# powerblade_test.net
KiCad netlist of a schematic drawn in EAGLE
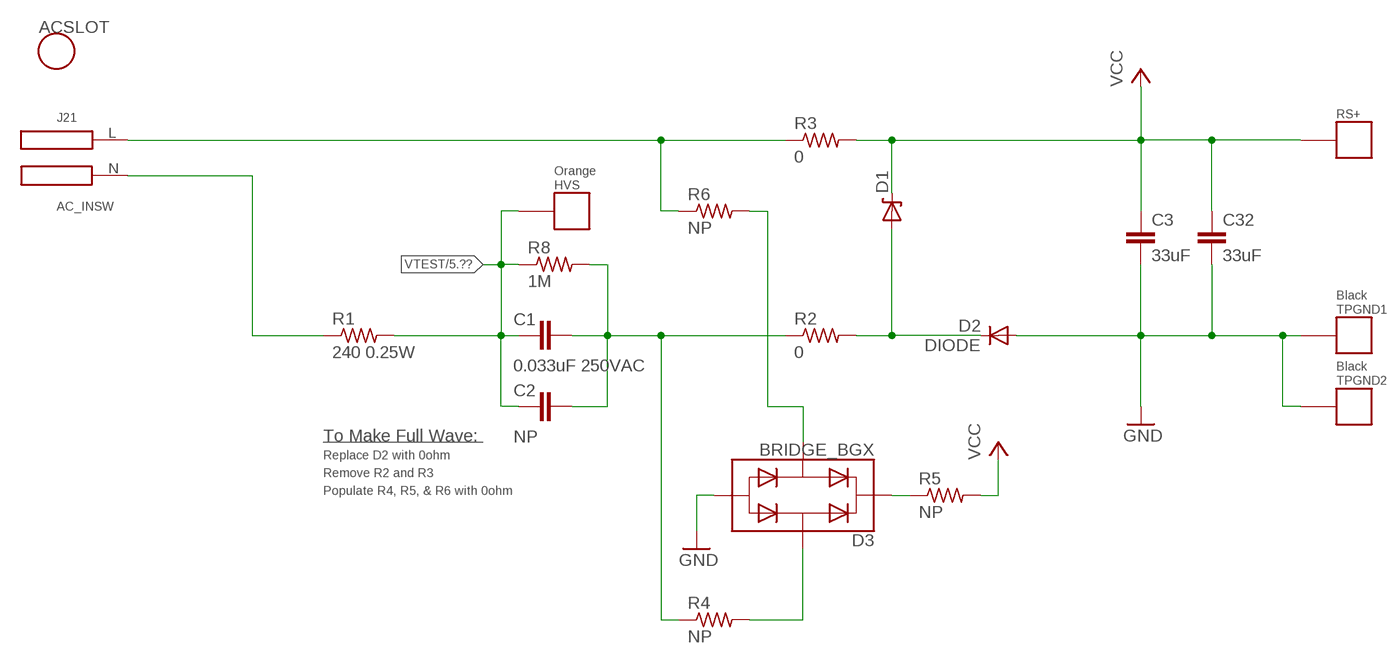
[diagram p0: schematic, sheet 1]
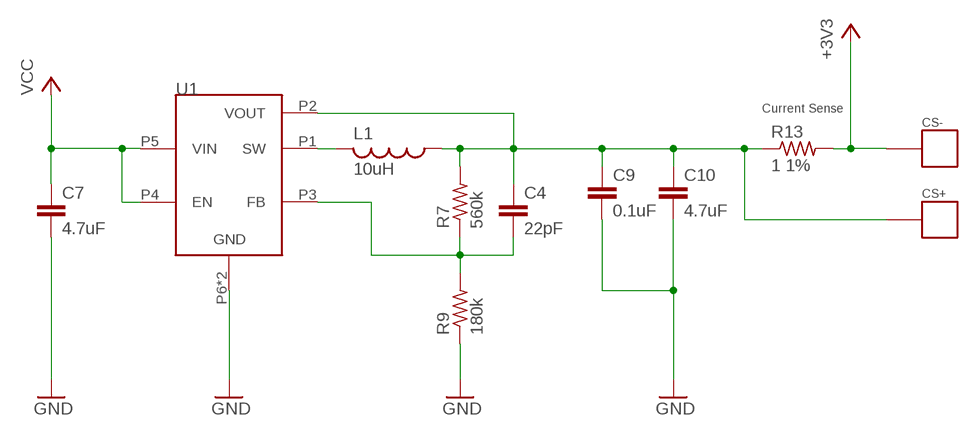
[diagram p1: schematic, sheet 2]
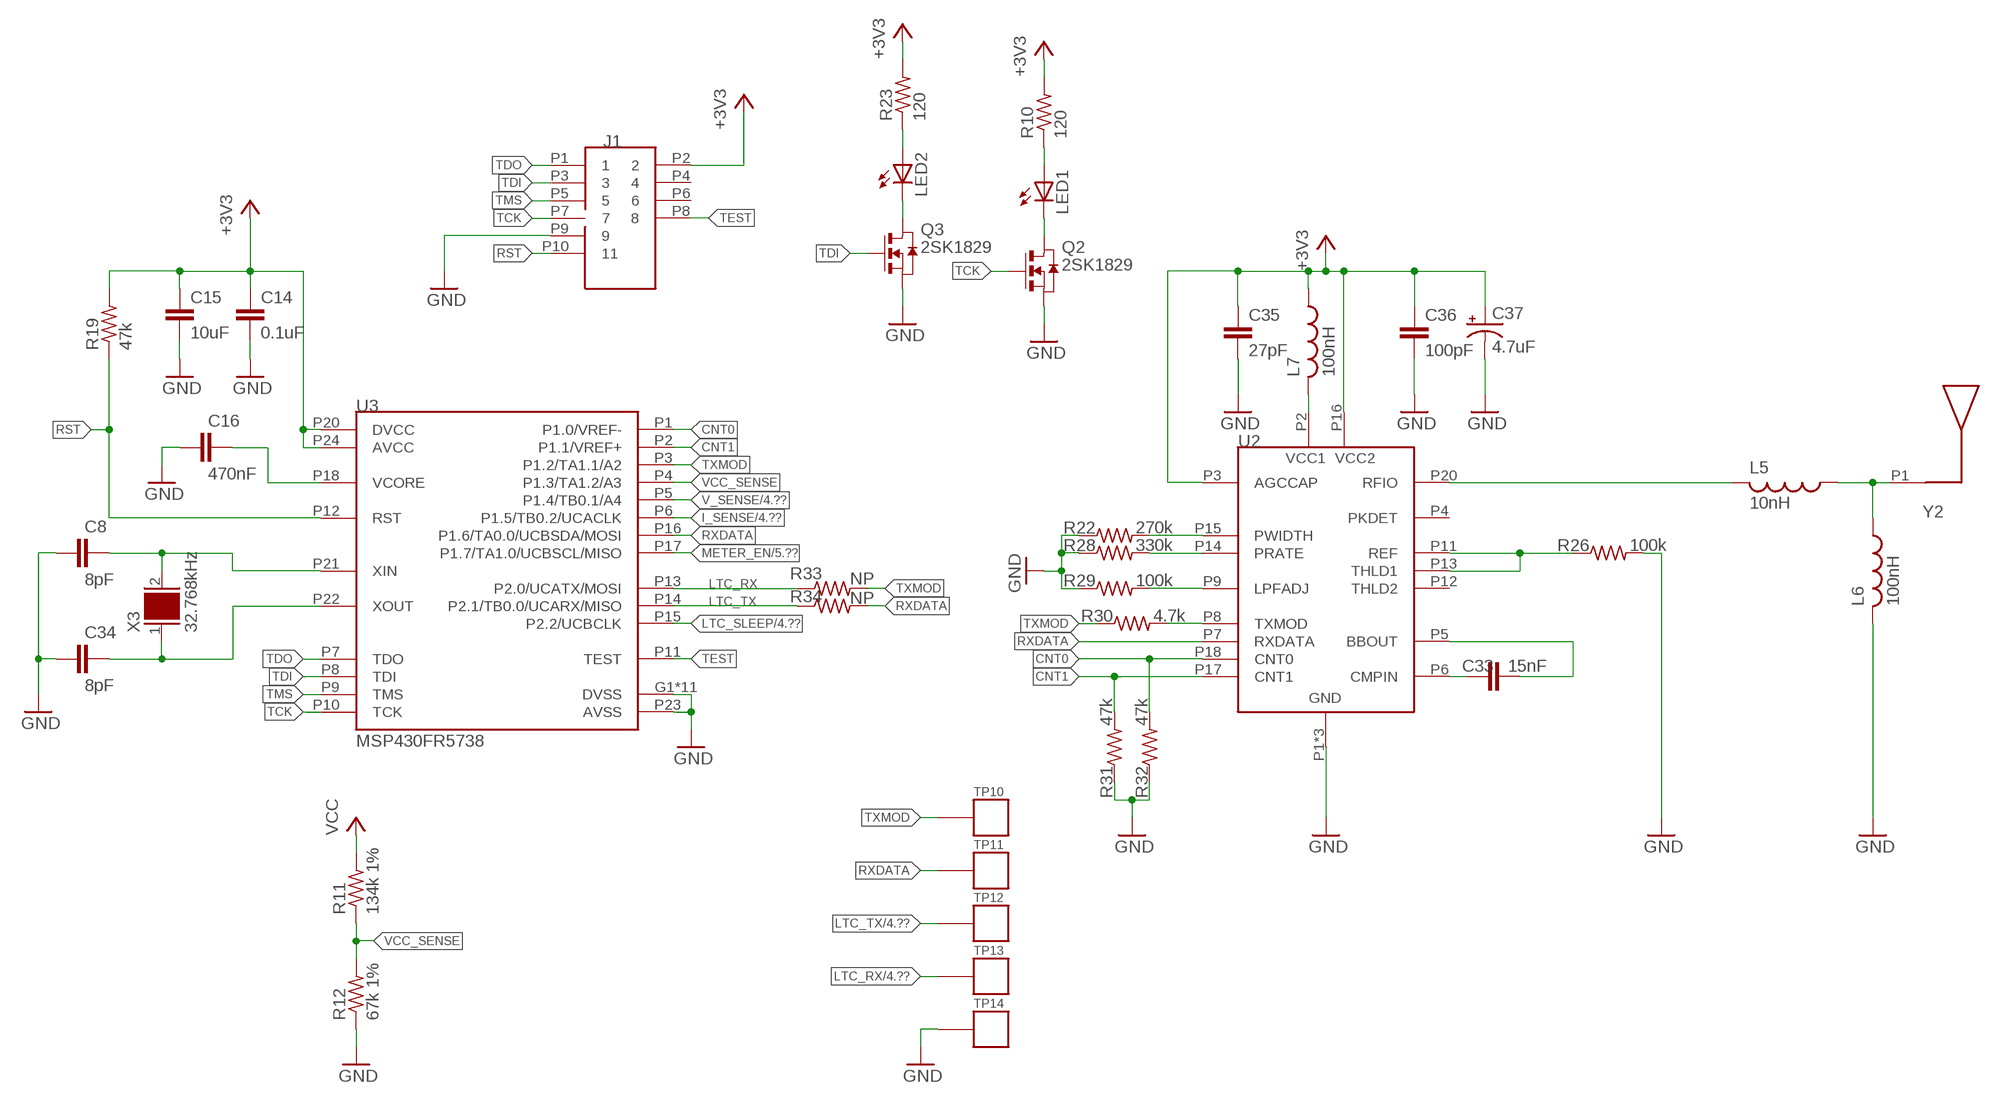
[diagram p2: schematic, sheet 3]
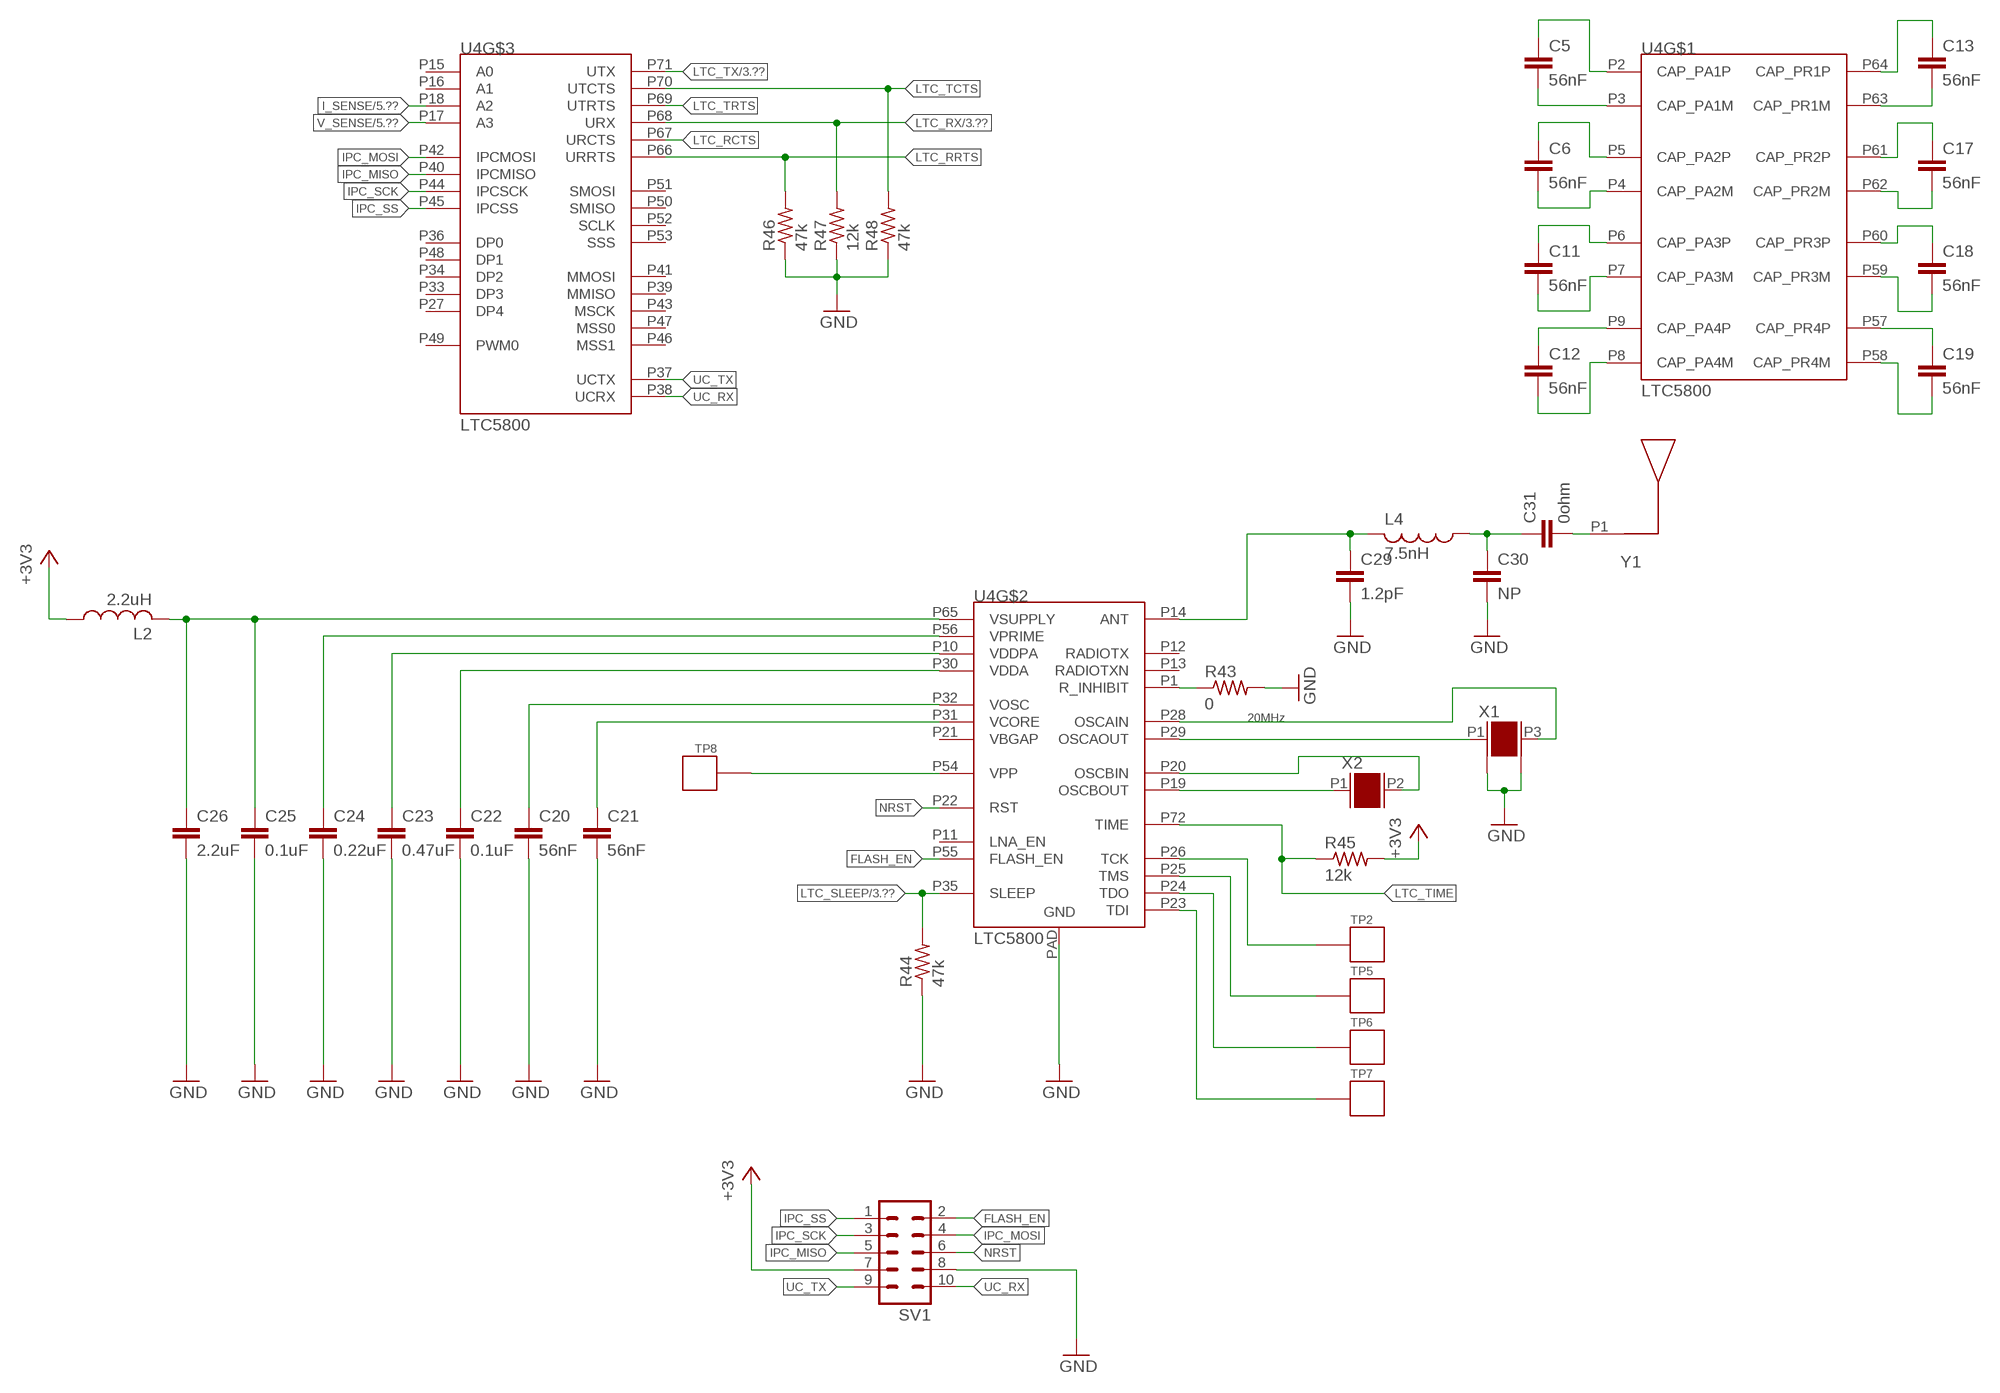
[diagram p3: schematic, sheet 4]
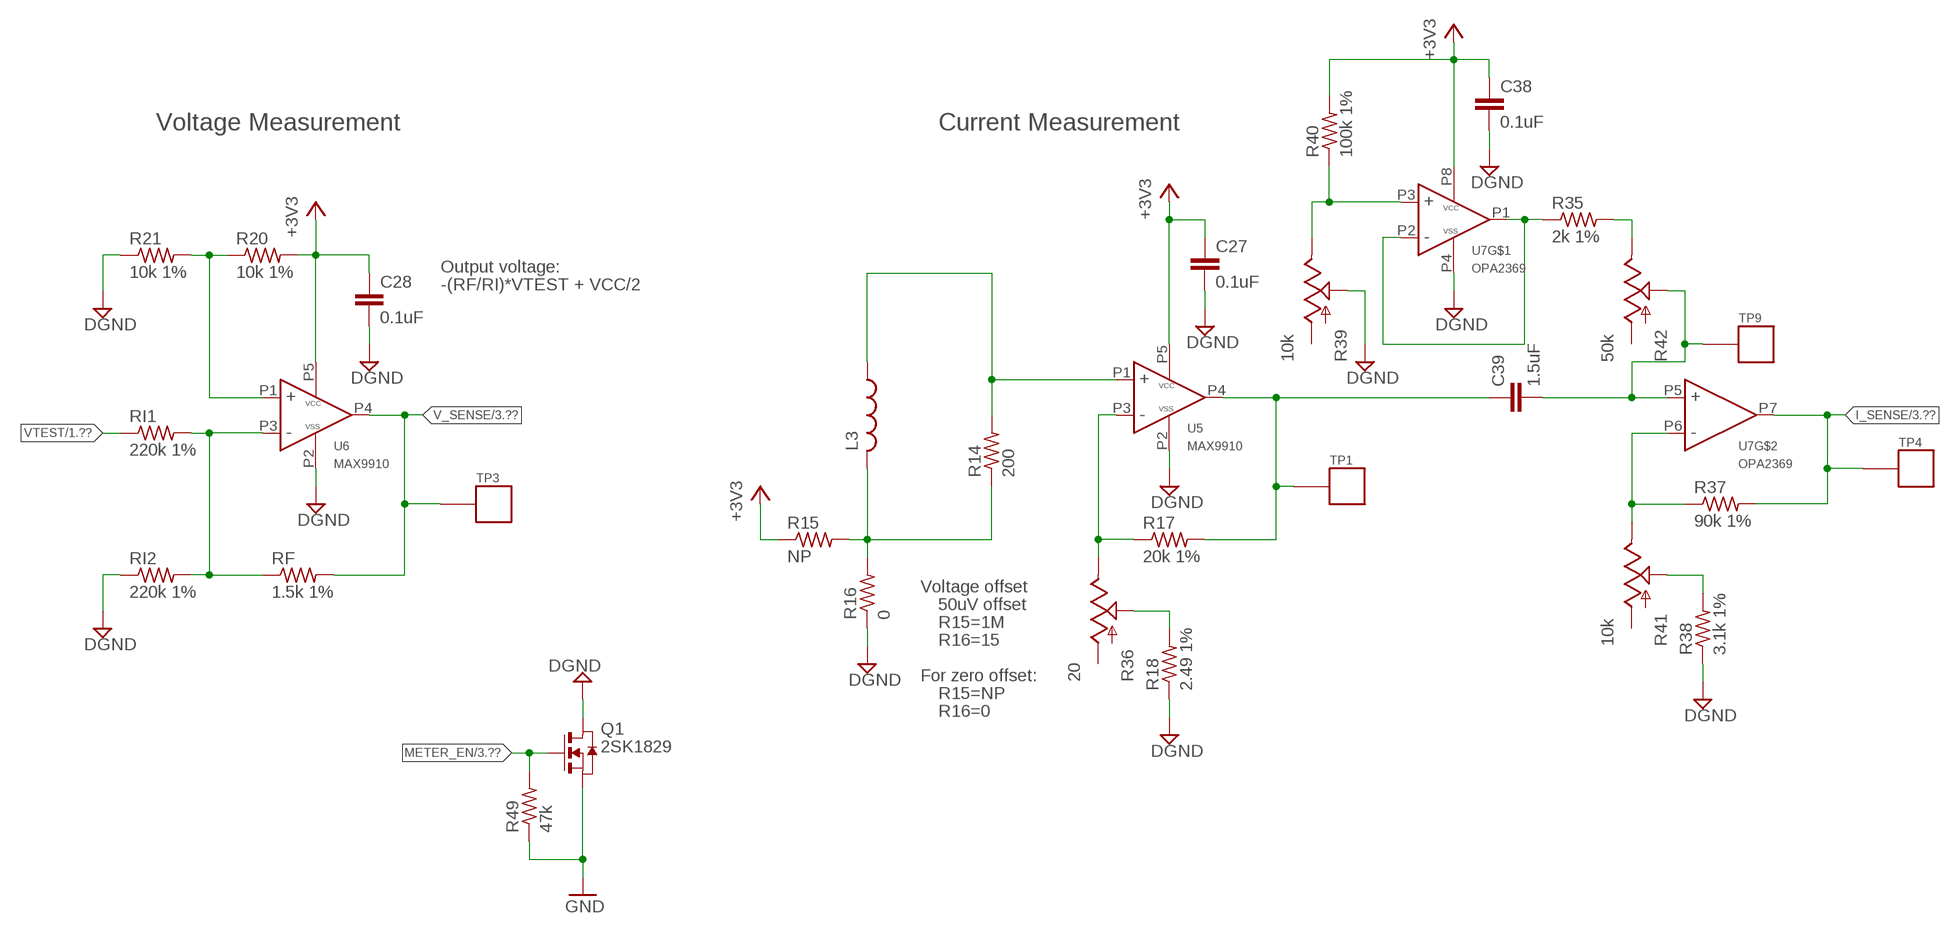
[diagram p4: schematic, sheet 5]

(export (version "E")
  (design (tool "Eeschema 10.0.6"))
  (components
    (comp (ref "C27")
      (value "0.1uF")
      (footprint "eagle-import:C0402")
      (libsource (lib "eagle-import") (part "C-EUC0402"))
    )
    (comp (ref "C28")
      (value "0.1uF")
      (footprint "eagle-import:C0402")
      (libsource (lib "eagle-import") (part "C-EUC0402"))
    )
    (comp (ref "C38")
      (value "0.1uF")
      (footprint "eagle-import:C0402")
      (libsource (lib "eagle-import") (part "C-EUC0402"))
    )
    (comp (ref "C39")
      (value "1.5uF")
      (footprint "eagle-import:C0402")
      (libsource (lib "eagle-import") (part "C-EUC0402"))
    )
    (comp (ref "L3")
      (value "L-USL0805")
      (footprint "eagle-import:L0805")
      (libsource (lib "eagle-import") (part "L-USL0805"))
    )
    (comp (ref "Q1")
      (value "2SK1829")
      (footprint "eagle-import:SC-70-3")
      (libsource (lib "eagle-import") (part "2SK1829"))
    )
    (comp (ref "R14")
      (value "200")
      (footprint "eagle-import:R0402")
      (libsource (lib "eagle-import") (part "R-US_R0402"))
    )
    (comp (ref "R15")
      (value "NP")
      (footprint "eagle-import:R0402")
      (libsource (lib "eagle-import") (part "R-US_R0402"))
    )
    (comp (ref "R16")
      (value "0")
      (footprint "eagle-import:R0402")
      (libsource (lib "eagle-import") (part "R-US_R0402"))
    )
    (comp (ref "R17")
      (value "20k 1%")
      (footprint "eagle-import:R0402")
      (libsource (lib "eagle-import") (part "R-US_R0402"))
    )
    (comp (ref "R18")
      (value "2.49 1%")
      (footprint "eagle-import:R0402")
      (libsource (lib "eagle-import") (part "R-US_R0402"))
    )
    (comp (ref "R20")
      (value "10k 1%")
      (footprint "eagle-import:R0402")
      (libsource (lib "eagle-import") (part "R-US_R0402"))
    )
    (comp (ref "R21")
      (value "10k 1%")
      (footprint "eagle-import:R0402")
      (libsource (lib "eagle-import") (part "R-US_R0402"))
    )
    (comp (ref "R35")
      (value "2k 1%")
      (footprint "eagle-import:R0402")
      (libsource (lib "eagle-import") (part "R-US_R0402"))
    )
    (comp (ref "R36")
      (value "20")
      (footprint "eagle-import:3313_POT")
      (libsource (lib "eagle-import") (part "3313_POT"))
    )
    (comp (ref "R37")
      (value "90k 1%")
      (footprint "eagle-import:R0402")
      (libsource (lib "eagle-import") (part "R-US_R0402"))
    )
    (comp (ref "R38")
      (value "3.1k 1%")
      (footprint "eagle-import:R0603")
      (libsource (lib "eagle-import") (part "R-US_R0603"))
    )
    (comp (ref "R39")
      (value "10k")
      (footprint "eagle-import:3313_POT")
      (libsource (lib "eagle-import") (part "3313_POT"))
    )
    (comp (ref "R40")
      (value "100k 1%")
      (footprint "eagle-import:R0402")
      (libsource (lib "eagle-import") (part "R-US_R0402"))
    )
    (comp (ref "R41")
      (value "10k")
      (footprint "eagle-import:3313_POT")
      (libsource (lib "eagle-import") (part "3313_POT"))
    )
    (comp (ref "R42")
      (value "50k")
      (footprint "eagle-import:3313_POT")
      (libsource (lib "eagle-import") (part "3313_POT"))
    )
    (comp (ref "R49")
      (value "47k")
      (footprint "eagle-import:R0603")
      (libsource (lib "eagle-import") (part "R-US_R0603"))
    )
    (comp (ref "RF")
      (value "1.5k 1%")
      (footprint "eagle-import:R0402")
      (libsource (lib "eagle-import") (part "R-US_R0402"))
    )
    (comp (ref "RI1")
      (value "220k 1%")
      (footprint "eagle-import:R0402")
      (libsource (lib "eagle-import") (part "R-US_R0402"))
    )
    (comp (ref "RI2")
      (value "220k 1%")
      (footprint "eagle-import:R0402")
      (libsource (lib "eagle-import") (part "R-US_R0402"))
    )
    (comp (ref "TP1")
      (value "TP_MULT")
      (footprint "eagle-import:TP_MULT")
      (libsource (lib "eagle-import") (part "TP_MULT"))
    )
    (comp (ref "TP3")
      (value "TP_MULT")
      (footprint "eagle-import:TP_MULT")
      (libsource (lib "eagle-import") (part "TP_MULT"))
    )
    (comp (ref "TP4")
      (value "TP_MULT")
      (footprint "eagle-import:TP_MULT")
      (libsource (lib "eagle-import") (part "TP_MULT"))
    )
    (comp (ref "TP9")
      (value "TP_MULT")
      (footprint "eagle-import:TP_MULT")
      (libsource (lib "eagle-import") (part "TP_MULT"))
    )
    (comp (ref "U5")
      (value "MAX9910")
      (footprint "eagle-import:SC70-5")
      (libsource (lib "eagle-import") (part "MAX9910"))
    )
    (comp (ref "U6")
      (value "MAX9910")
      (footprint "eagle-import:SC70-5")
      (libsource (lib "eagle-import") (part "MAX9910"))
    )
    (comp (ref "U7")
      (value "OPA2369")
      (footprint "eagle-import:SOT-23-8")
      (libsource (lib "eagle-import") (part "OPA2369"))
    )
    (comp (ref "C5")
      (value "56nF")
      (footprint "eagle-import:C0402")
      (libsource (lib "eagle-import") (part "C-EUC0402"))
    )
    (comp (ref "C6")
      (value "56nF")
      (footprint "eagle-import:C0402")
      (libsource (lib "eagle-import") (part "C-EUC0402"))
    )
    (comp (ref "C11")
      (value "56nF")
      (footprint "eagle-import:C0402")
      (libsource (lib "eagle-import") (part "C-EUC0402"))
    )
    (comp (ref "C12")
      (value "56nF")
      (footprint "eagle-import:C0402")
      (libsource (lib "eagle-import") (part "C-EUC0402"))
    )
    (comp (ref "C13")
      (value "56nF")
      (footprint "eagle-import:C0402")
      (libsource (lib "eagle-import") (part "C-EUC0402"))
    )
    (comp (ref "C17")
      (value "56nF")
      (footprint "eagle-import:C0402")
      (libsource (lib "eagle-import") (part "C-EUC0402"))
    )
    (comp (ref "C18")
      (value "56nF")
      (footprint "eagle-import:C0402")
      (libsource (lib "eagle-import") (part "C-EUC0402"))
    )
    (comp (ref "C19")
      (value "56nF")
      (footprint "eagle-import:C0402")
      (libsource (lib "eagle-import") (part "C-EUC0402"))
    )
    (comp (ref "C20")
      (value "56nF")
      (footprint "eagle-import:C0402")
      (libsource (lib "eagle-import") (part "C-EUC0402"))
    )
    (comp (ref "C21")
      (value "56nF")
      (footprint "eagle-import:C0402")
      (libsource (lib "eagle-import") (part "C-EUC0402"))
    )
    (comp (ref "C22")
      (value "0.1uF")
      (footprint "eagle-import:C0603")
      (libsource (lib "eagle-import") (part "C-EUC0603"))
    )
    (comp (ref "C23")
      (value "0.47uF")
      (footprint "eagle-import:C0603")
      (libsource (lib "eagle-import") (part "C-EUC0603"))
    )
    (comp (ref "C24")
      (value "0.22uF")
      (footprint "eagle-import:C0603")
      (libsource (lib "eagle-import") (part "C-EUC0603"))
    )
    (comp (ref "C25")
      (value "0.1uF")
      (footprint "eagle-import:C0603")
      (libsource (lib "eagle-import") (part "C-EUC0603"))
    )
    (comp (ref "C26")
      (value "2.2uF")
      (footprint "eagle-import:C0603")
      (libsource (lib "eagle-import") (part "C-EUC0603"))
    )
    (comp (ref "C29")
      (value "1.2pF")
      (footprint "eagle-import:C0402")
      (libsource (lib "eagle-import") (part "C-EUC0402"))
    )
    (comp (ref "C30")
      (value "NP")
      (footprint "eagle-import:C0402")
      (libsource (lib "eagle-import") (part "C-EUC0402"))
    )
    (comp (ref "C31")
      (value "0ohm")
      (footprint "eagle-import:C0402")
      (libsource (lib "eagle-import") (part "C-EUC0402"))
    )
    (comp (ref "L2")
      (value "2.2uH")
      (footprint "eagle-import:L0603")
      (libsource (lib "eagle-import") (part "L-USL0603"))
    )
    (comp (ref "L4")
      (value "7.5nH")
      (footprint "eagle-import:L0402")
      (libsource (lib "eagle-import") (part "L-USL0402"))
    )
    (comp (ref "R43")
      (value "0")
      (footprint "eagle-import:R0402")
      (libsource (lib "eagle-import") (part "R-US_R0402"))
    )
    (comp (ref "R44")
      (value "47k")
      (footprint "eagle-import:R0402")
      (libsource (lib "eagle-import") (part "R-US_R0402"))
    )
    (comp (ref "R45")
      (value "12k")
      (footprint "eagle-import:R0402")
      (libsource (lib "eagle-import") (part "R-US_R0402"))
    )
    (comp (ref "R46")
      (value "47k")
      (footprint "eagle-import:R0402")
      (libsource (lib "eagle-import") (part "R-US_R0402"))
    )
    (comp (ref "R47")
      (value "12k")
      (footprint "eagle-import:R0402")
      (libsource (lib "eagle-import") (part "R-US_R0402"))
    )
    (comp (ref "R48")
      (value "47k")
      (footprint "eagle-import:R0402")
      (libsource (lib "eagle-import") (part "R-US_R0402"))
    )
    (comp (ref "SV1")
      (value "MA05-2KEY")
      (footprint "eagle-import:MA05-2_KEY")
      (libsource (lib "eagle-import") (part "MA05-2KEY"))
    )
    (comp (ref "TP2")
      (value "TP_SMD")
      (footprint "eagle-import:TP_SMD")
      (libsource (lib "eagle-import") (part "TP_SMD"))
    )
    (comp (ref "TP5")
      (value "TP_SMD")
      (footprint "eagle-import:TP_SMD")
      (libsource (lib "eagle-import") (part "TP_SMD"))
    )
    (comp (ref "TP6")
      (value "TP_SMD")
      (footprint "eagle-import:TP_SMD")
      (libsource (lib "eagle-import") (part "TP_SMD"))
    )
    (comp (ref "TP7")
      (value "TP_SMD")
      (footprint "eagle-import:TP_SMD")
      (libsource (lib "eagle-import") (part "TP_SMD"))
    )
    (comp (ref "TP8")
      (value "TP_STD")
      (footprint "eagle-import:TP")
      (libsource (lib "eagle-import") (part "TP_STD"))
    )
    (comp (ref "U4")
      (value "LTC5800")
      (footprint "eagle-import:QFN-72")
      (libsource (lib "eagle-import") (part "LTC5800"))
    )
    (comp (ref "X1")
      (value "ABM8G")
      (footprint "eagle-import:ABM8G")
      (libsource (lib "eagle-import") (part "ABM8G"))
    )
    (comp (ref "X2")
      (value "ABS07")
      (footprint "eagle-import:ABS07")
      (libsource (lib "eagle-import") (part "ABS07"))
    )
    (comp (ref "Y1")
      (value "UREACH_XTEND")
      (footprint "eagle-import:UREACH_XTEND")
      (libsource (lib "eagle-import") (part "UREACH_XTEND"))
    )
    (comp (ref "ACSLOT")
      (value "AC_NODIM")
      (footprint "eagle-import:AC3_NODIM")
      (libsource (lib "eagle-import") (part "AC_NODIM"))
    )
    (comp (ref "C1")
      (value "0.033uF 250VAC")
      (footprint "eagle-import:C2220K")
      (libsource (lib "eagle-import") (part "C-EUC2220K"))
    )
    (comp (ref "C2")
      (value "NP")
      (footprint "eagle-import:C2220K")
      (libsource (lib "eagle-import") (part "C-EUC2220K"))
    )
    (comp (ref "C3")
      (value "33uF")
      (footprint "eagle-import:C0603")
      (libsource (lib "eagle-import") (part "C-EUC0603"))
    )
    (comp (ref "C32")
      (value "33uF")
      (footprint "eagle-import:C0603")
      (libsource (lib "eagle-import") (part "C-EUC0603"))
    )
    (comp (ref "D1")
      (value "ZENERBZT52")
      (footprint "eagle-import:BZT52")
      (fields (field (name "DIGIKEY") "NP"))
      (libsource (lib "eagle-import") (part "ZENERBZT52"))
    )
    (comp (ref "D2")
      (value "DIODE")
      (footprint "eagle-import:BAS521")
      (fields (field (name "DIGIKEY") "NP"))
      (libsource (lib "eagle-import") (part "DIODE"))
    )
    (comp (ref "D3")
      (value "BRIDGE_BGX")
      (footprint "eagle-import:TO-253-4")
      (fields (field (name "DIGIKEY") "NP"))
      (libsource (lib "eagle-import") (part "BRIDGE_BGX"))
    )
    (comp (ref "HVS")
      (value "TP_MULT")
      (footprint "eagle-import:TP_MULT")
      (libsource (lib "eagle-import") (part "TP_MULT"))
    )
    (comp (ref "J21")
      (value "AC_INSW")
      (footprint "eagle-import:AC_DC21")
      (fields (field (name "DIGIKEY") "NP"))
      (libsource (lib "eagle-import") (part "AC_INSW"))
    )
    (comp (ref "R1")
      (value "240 0.25W")
      (footprint "eagle-import:R0603")
      (libsource (lib "eagle-import") (part "R-US_R0603"))
    )
    (comp (ref "R2")
      (value "0")
      (footprint "eagle-import:R0603")
      (libsource (lib "eagle-import") (part "R-US_R0603"))
    )
    (comp (ref "R3")
      (value "0")
      (footprint "eagle-import:R0603")
      (libsource (lib "eagle-import") (part "R-US_R0603"))
    )
    (comp (ref "R4")
      (value "NP")
      (footprint "eagle-import:R0603")
      (libsource (lib "eagle-import") (part "R-US_R0603"))
    )
    (comp (ref "R5")
      (value "NP")
      (footprint "eagle-import:R0603")
      (libsource (lib "eagle-import") (part "R-US_R0603"))
    )
    (comp (ref "R6")
      (value "NP")
      (footprint "eagle-import:R0603")
      (libsource (lib "eagle-import") (part "R-US_R0603"))
    )
    (comp (ref "R8")
      (value "1M")
      (footprint "eagle-import:R0603")
      (libsource (lib "eagle-import") (part "R-US_R0603"))
    )
    (comp (ref "RS+")
      (value "TP_MULT")
      (footprint "eagle-import:TP_MULT")
      (libsource (lib "eagle-import") (part "TP_MULT"))
    )
    (comp (ref "TPGND1")
      (value "TP_MULT")
      (footprint "eagle-import:TP_MULT")
      (libsource (lib "eagle-import") (part "TP_MULT"))
    )
    (comp (ref "TPGND2")
      (value "TP_MULT")
      (footprint "eagle-import:TP_MULT")
      (libsource (lib "eagle-import") (part "TP_MULT"))
    )
    (comp (ref "C4")
      (value "22pF")
      (footprint "eagle-import:C0402")
      (libsource (lib "eagle-import") (part "C-EUC0402"))
    )
    (comp (ref "C7")
      (value "4.7uF")
      (footprint "eagle-import:C0603")
      (libsource (lib "eagle-import") (part "C-EUC0603"))
    )
    (comp (ref "C9")
      (value "0.1uF")
      (footprint "eagle-import:C0402")
      (libsource (lib "eagle-import") (part "C-EUC0402"))
    )
    (comp (ref "C10")
      (value "4.7uF")
      (footprint "eagle-import:C0402")
      (libsource (lib "eagle-import") (part "C-EUC0402"))
    )
    (comp (ref "CS+")
      (value "TP_MULT")
      (footprint "eagle-import:TP_MULT")
      (libsource (lib "eagle-import") (part "TP_MULT"))
    )
    (comp (ref "CS-")
      (value "TP_MULT")
      (footprint "eagle-import:TP_MULT")
      (libsource (lib "eagle-import") (part "TP_MULT"))
    )
    (comp (ref "L1")
      (value "10uH")
      (footprint "eagle-import:L0805")
      (libsource (lib "eagle-import") (part "L-USL0805"))
    )
    (comp (ref "R7")
      (value "560k")
      (footprint "eagle-import:R0402")
      (libsource (lib "eagle-import") (part "R-US_R0402"))
    )
    (comp (ref "R9")
      (value "180k")
      (footprint "eagle-import:R0402")
      (libsource (lib "eagle-import") (part "R-US_R0402"))
    )
    (comp (ref "R13")
      (value "1 1%")
      (footprint "eagle-import:R0603")
      (libsource (lib "eagle-import") (part "R-US_R0603"))
    )
    (comp (ref "U1")
      (value "TPS62122")
      (footprint "eagle-import:WDFN-6")
      (libsource (lib "eagle-import") (part "TPS62122"))
    )
    (comp (ref "C8")
      (value "8pF")
      (footprint "eagle-import:C0603")
      (libsource (lib "eagle-import") (part "C-EUC0603"))
    )
    (comp (ref "C14")
      (value "0.1uF")
      (footprint "eagle-import:C0603")
      (libsource (lib "eagle-import") (part "C-EUC0603"))
    )
    (comp (ref "C15")
      (value "10uF")
      (footprint "eagle-import:C0603")
      (libsource (lib "eagle-import") (part "C-EUC0603"))
    )
    (comp (ref "C16")
      (value "470nF")
      (footprint "eagle-import:C0603")
      (libsource (lib "eagle-import") (part "C-EUC0603"))
    )
    (comp (ref "C33")
      (value "15nF")
      (footprint "eagle-import:C0603")
      (libsource (lib "eagle-import") (part "C-EUC0603"))
    )
    (comp (ref "C34")
      (value "8pF")
      (footprint "eagle-import:C0603")
      (libsource (lib "eagle-import") (part "C-EUC0603"))
    )
    (comp (ref "C35")
      (value "27pF")
      (footprint "eagle-import:C0603")
      (libsource (lib "eagle-import") (part "C-EUC0603"))
    )
    (comp (ref "C36")
      (value "100pF")
      (footprint "eagle-import:C0603")
      (libsource (lib "eagle-import") (part "C-EUC0603"))
    )
    (comp (ref "C37")
      (value "4.7uF")
      (footprint "eagle-import:CPOL-0805")
      (libsource (lib "eagle-import") (part "CPOL-US0805"))
    )
    (comp (ref "J1")
      (value "JTAG_14PIN_IDC")
      (footprint "eagle-import:TC2050-IDC-430")
      (libsource (lib "eagle-import") (part "JTAG_14PIN_IDC"))
    )
    (comp (ref "L5")
      (value "10nH")
      (footprint "eagle-import:L0402")
      (libsource (lib "eagle-import") (part "L-USL0402"))
    )
    (comp (ref "L6")
      (value "100nH")
      (footprint "eagle-import:L0402")
      (libsource (lib "eagle-import") (part "L-USL0402"))
    )
    (comp (ref "L7")
      (value "100nH")
      (footprint "eagle-import:L0603")
      (libsource (lib "eagle-import") (part "L-USL0603"))
    )
    (comp (ref "LED1")
      (value "LED0603")
      (footprint "eagle-import:LED-0603")
      (libsource (lib "eagle-import") (part "LED0603"))
    )
    (comp (ref "LED2")
      (value "LED0603")
      (footprint "eagle-import:LED-0603")
      (libsource (lib "eagle-import") (part "LED0603"))
    )
    (comp (ref "Q2")
      (value "2SK1829")
      (footprint "eagle-import:SC-70-3")
      (libsource (lib "eagle-import") (part "2SK1829"))
    )
    (comp (ref "Q3")
      (value "2SK1829")
      (footprint "eagle-import:SC-70-3")
      (libsource (lib "eagle-import") (part "2SK1829"))
    )
    (comp (ref "R10")
      (value "120")
      (footprint "eagle-import:R0603")
      (libsource (lib "eagle-import") (part "R-US_R0603"))
    )
    (comp (ref "R11")
      (value "134k 1%")
      (footprint "eagle-import:R0603")
      (libsource (lib "eagle-import") (part "R-US_R0603"))
    )
    (comp (ref "R12")
      (value "67k 1%")
      (footprint "eagle-import:R0603")
      (libsource (lib "eagle-import") (part "R-US_R0603"))
    )
    (comp (ref "R19")
      (value "47k")
      (footprint "eagle-import:R0603")
      (libsource (lib "eagle-import") (part "R-US_R0603"))
    )
    (comp (ref "R22")
      (value "270k")
      (footprint "eagle-import:R0603")
      (libsource (lib "eagle-import") (part "R-US_R0603"))
    )
    (comp (ref "R23")
      (value "120")
      (footprint "eagle-import:R0603")
      (libsource (lib "eagle-import") (part "R-US_R0603"))
    )
    (comp (ref "R26")
      (value "100k")
      (footprint "eagle-import:R0603")
      (libsource (lib "eagle-import") (part "R-US_R0603"))
    )
    (comp (ref "R28")
      (value "330k")
      (footprint "eagle-import:R0603")
      (libsource (lib "eagle-import") (part "R-US_R0603"))
    )
    (comp (ref "R29")
      (value "100k")
      (footprint "eagle-import:R0603")
      (libsource (lib "eagle-import") (part "R-US_R0603"))
    )
    (comp (ref "R30")
      (value "4.7k")
      (footprint "eagle-import:R0603")
      (libsource (lib "eagle-import") (part "R-US_R0603"))
    )
    (comp (ref "R31")
      (value "47k")
      (footprint "eagle-import:R0603")
      (libsource (lib "eagle-import") (part "R-US_R0603"))
    )
    (comp (ref "R32")
      (value "47k")
      (footprint "eagle-import:R0603")
      (libsource (lib "eagle-import") (part "R-US_R0603"))
    )
    (comp (ref "R33")
      (value "NP")
      (footprint "eagle-import:R0603")
      (libsource (lib "eagle-import") (part "R-US_R0603"))
    )
    (comp (ref "R34")
      (value "NP")
      (footprint "eagle-import:R0603")
      (libsource (lib "eagle-import") (part "R-US_R0603"))
    )
    (comp (ref "TP10")
      (value "TP_STD")
      (footprint "eagle-import:TP")
      (libsource (lib "eagle-import") (part "TP_STD"))
    )
    (comp (ref "TP11")
      (value "TP_STD")
      (footprint "eagle-import:TP")
      (libsource (lib "eagle-import") (part "TP_STD"))
    )
    (comp (ref "TP12")
      (value "TP_STD")
      (footprint "eagle-import:TP")
      (libsource (lib "eagle-import") (part "TP_STD"))
    )
    (comp (ref "TP13")
      (value "TP_STD")
      (footprint "eagle-import:TP")
      (libsource (lib "eagle-import") (part "TP_STD"))
    )
    (comp (ref "TP14")
      (value "TP_STD")
      (footprint "eagle-import:TP")
      (libsource (lib "eagle-import") (part "TP_STD"))
    )
    (comp (ref "U2")
      (value "TR1000")
      (footprint "eagle-import:SM-20H")
      (libsource (lib "eagle-import") (part "TR1000"))
    )
    (comp (ref "U3")
      (value "MSP430FR5738")
      (footprint "eagle-import:VQFN-24")
      (libsource (lib "eagle-import") (part "MSP430FR5738"))
    )
    (comp (ref "X3")
      (value "32.768kHz")
      (footprint "eagle-import:0805")
      (libsource (lib "eagle-import") (part "CRYSTAL_0805"))
    )
    (comp (ref "Y2")
      (value "ANT-916")
      (footprint "eagle-import:ANT-916")
      (libsource (lib "eagle-import") (part "ANT-916"))
    )
  )
  (nets
    (net (code "1") (name "+3V3") (class "Default")
      (node (ref "C14") (pin "1") (pinfunction "1_1") (pintype "passive"))
      (node (ref "C15") (pin "1") (pinfunction "1_1") (pintype "passive"))
      (node (ref "C27") (pin "1") (pinfunction "1_1") (pintype "passive"))
      (node (ref "C28") (pin "1") (pinfunction "1_1") (pintype "passive"))
      (node (ref "C35") (pin "1") (pinfunction "1_1") (pintype "passive"))
      (node (ref "C36") (pin "1") (pinfunction "1_1") (pintype "passive"))
      (node (ref "C37") (pin "+") (pinfunction "+_+") (pintype "passive"))
      (node (ref "C38") (pin "1") (pinfunction "1_1") (pintype "passive"))
      (node (ref "CS-") (pin "P$1") (pinfunction "P$1_P$1") (pintype "bidirectional"))
      (node (ref "J1") (pin "P2") (pinfunction "2_P2") (pintype "bidirectional"))
      (node (ref "L2") (pin "1") (pinfunction "1_1") (pintype "passive"))
      (node (ref "L7") (pin "1") (pinfunction "1_1") (pintype "passive"))
      (node (ref "R10") (pin "2") (pinfunction "2_2") (pintype "passive"))
      (node (ref "R13") (pin "2") (pinfunction "2_2") (pintype "passive"))
      (node (ref "R15") (pin "1") (pinfunction "1_1") (pintype "passive"))
      (node (ref "R19") (pin "2") (pinfunction "2_2") (pintype "passive"))
      (node (ref "R20") (pin "2") (pinfunction "2_2") (pintype "passive"))
      (node (ref "R23") (pin "2") (pinfunction "2_2") (pintype "passive"))
      (node (ref "R40") (pin "2") (pinfunction "2_2") (pintype "passive"))
      (node (ref "R45") (pin "2") (pinfunction "2_2") (pintype "passive"))
      (node (ref "SV1") (pin "7") (pinfunction "7_7") (pintype "passive"))
      (node (ref "U2") (pin "P16") (pinfunction "VCC2_P16") (pintype "bidirectional"))
      (node (ref "U2") (pin "P3") (pinfunction "AGCCAP_P3") (pintype "bidirectional"))
      (node (ref "U3") (pin "P20") (pinfunction "DVCC_P20") (pintype "bidirectional"))
      (node (ref "U3") (pin "P24") (pinfunction "AVCC_P24") (pintype "bidirectional"))
      (node (ref "U5") (pin "P5") (pinfunction "VCC_P5") (pintype "bidirectional"))
      (node (ref "U6") (pin "P5") (pinfunction "VCC_P5") (pintype "bidirectional"))
      (node (ref "U7") (pin "P8") (pinfunction "VCC_P8") (pintype "bidirectional"))
    )
    (net (code "2") (name "CNT0") (class "Default")
      (node (ref "R32") (pin "2") (pinfunction "2_2") (pintype "passive"))
      (node (ref "U2") (pin "P18") (pinfunction "CNT0_P18") (pintype "bidirectional"))
      (node (ref "U3") (pin "P1") (pinfunction "P1.0/VREF-_P1") (pintype "bidirectional"))
    )
    (net (code "3") (name "CNT1") (class "Default")
      (node (ref "R31") (pin "2") (pinfunction "2_2") (pintype "passive"))
      (node (ref "U2") (pin "P17") (pinfunction "CNT1_P17") (pintype "bidirectional"))
      (node (ref "U3") (pin "P2") (pinfunction "P1.1/VREF+_P2") (pintype "bidirectional"))
    )
    (net (code "4") (name "DGND") (class "Default")
      (node (ref "C27") (pin "2") (pinfunction "2_2") (pintype "passive"))
      (node (ref "C28") (pin "2") (pinfunction "2_2") (pintype "passive"))
      (node (ref "C38") (pin "2") (pinfunction "2_2") (pintype "passive"))
      (node (ref "Q1") (pin "P3") (pinfunction "D_P3") (pintype "passive"))
      (node (ref "R16") (pin "1") (pinfunction "1_1") (pintype "passive"))
      (node (ref "R18") (pin "1") (pinfunction "1_1") (pintype "passive"))
      (node (ref "R21") (pin "1") (pinfunction "1_1") (pintype "passive"))
      (node (ref "R38") (pin "1") (pinfunction "1_1") (pintype "passive"))
      (node (ref "R39") (pin "PW") (pinfunction "PW_PW") (pintype "passive"))
      (node (ref "RI2") (pin "1") (pinfunction "1_1") (pintype "passive"))
      (node (ref "U5") (pin "P2") (pinfunction "VSS_P2") (pintype "bidirectional"))
      (node (ref "U6") (pin "P2") (pinfunction "VSS_P2") (pintype "bidirectional"))
      (node (ref "U7") (pin "P4") (pinfunction "VSS_P4") (pintype "bidirectional"))
    )
    (net (code "5") (name "FLASH_EN") (class "Default")
      (node (ref "SV1") (pin "2") (pinfunction "2_2") (pintype "passive"))
      (node (ref "U4") (pin "P55") (pinfunction "FLASH_EN_P55") (pintype "bidirectional"))
    )
    (net (code "6") (name "GND") (class "Default")
      (node (ref "C10") (pin "2") (pinfunction "2_2") (pintype "passive"))
      (node (ref "C14") (pin "2") (pinfunction "2_2") (pintype "passive"))
      (node (ref "C15") (pin "2") (pinfunction "2_2") (pintype "passive"))
      (node (ref "C16") (pin "1") (pinfunction "1_1") (pintype "passive"))
      (node (ref "C20") (pin "2") (pinfunction "2_2") (pintype "passive"))
      (node (ref "C21") (pin "2") (pinfunction "2_2") (pintype "passive"))
      (node (ref "C22") (pin "2") (pinfunction "2_2") (pintype "passive"))
      (node (ref "C23") (pin "2") (pinfunction "2_2") (pintype "passive"))
      (node (ref "C24") (pin "2") (pinfunction "2_2") (pintype "passive"))
      (node (ref "C25") (pin "2") (pinfunction "2_2") (pintype "passive"))
      (node (ref "C26") (pin "2") (pinfunction "2_2") (pintype "passive"))
      (node (ref "C29") (pin "2") (pinfunction "2_2") (pintype "passive"))
      (node (ref "C3") (pin "2") (pinfunction "2_2") (pintype "passive"))
      (node (ref "C30") (pin "2") (pinfunction "2_2") (pintype "passive"))
      (node (ref "C32") (pin "2") (pinfunction "2_2") (pintype "passive"))
      (node (ref "C34") (pin "1") (pinfunction "1_1") (pintype "passive"))
      (node (ref "C35") (pin "2") (pinfunction "2_2") (pintype "passive"))
      (node (ref "C36") (pin "2") (pinfunction "2_2") (pintype "passive"))
      (node (ref "C37") (pin "-") (pinfunction "-_-") (pintype "passive"))
      (node (ref "C7") (pin "2") (pinfunction "2_2") (pintype "passive"))
      (node (ref "C8") (pin "1") (pinfunction "1_1") (pintype "passive"))
      (node (ref "C9") (pin "2") (pinfunction "2_2") (pintype "passive"))
      (node (ref "D2") (pin "A") (pinfunction "A_A") (pintype "passive"))
      (node (ref "D3") (pin "P3") (pinfunction "P3_P3") (pintype "passive"))
      (node (ref "J1") (pin "P9") (pinfunction "9_P9") (pintype "bidirectional"))
      (node (ref "L6") (pin "2") (pinfunction "2_2") (pintype "passive"))
      (node (ref "Q1") (pin "P2") (pinfunction "S_P2") (pintype "passive"))
      (node (ref "Q2") (pin "P2") (pinfunction "S_P2") (pintype "passive"))
      (node (ref "Q3") (pin "P2") (pinfunction "S_P2") (pintype "passive"))
      (node (ref "R12") (pin "1") (pinfunction "1_1") (pintype "passive"))
      (node (ref "R22") (pin "1") (pinfunction "1_1") (pintype "passive"))
      (node (ref "R26") (pin "2") (pinfunction "2_2") (pintype "passive"))
      (node (ref "R28") (pin "1") (pinfunction "1_1") (pintype "passive"))
      (node (ref "R29") (pin "1") (pinfunction "1_1") (pintype "passive"))
      (node (ref "R31") (pin "1") (pinfunction "1_1") (pintype "passive"))
      (node (ref "R32") (pin "1") (pinfunction "1_1") (pintype "passive"))
      (node (ref "R43") (pin "2") (pinfunction "2_2") (pintype "passive"))
      (node (ref "R44") (pin "1") (pinfunction "1_1") (pintype "passive"))
      (node (ref "R46") (pin "1") (pinfunction "1_1") (pintype "passive"))
      (node (ref "R47") (pin "1") (pinfunction "1_1") (pintype "passive"))
      (node (ref "R48") (pin "1") (pinfunction "1_1") (pintype "passive"))
      (node (ref "R49") (pin "1") (pinfunction "1_1") (pintype "passive"))
      (node (ref "R9") (pin "1") (pinfunction "1_1") (pintype "passive"))
      (node (ref "SV1") (pin "8") (pinfunction "8_8") (pintype "passive"))
      (node (ref "TP14") (pin "P$1") (pinfunction "P$1_P$1") (pintype "bidirectional"))
      (node (ref "TPGND1") (pin "P$1") (pinfunction "P$1_P$1") (pintype "bidirectional"))
      (node (ref "TPGND2") (pin "P$1") (pinfunction "P$1_P$1") (pintype "bidirectional"))
      (node (ref "U1") (pin "P6") (pinfunction "GND_P6") (pintype "bidirectional"))
      (node (ref "U1") (pin "PAD") (pinfunction "GND_PAD") (pintype "bidirectional"))
      (node (ref "U2") (pin "P1") (pinfunction "GND_P1") (pintype "bidirectional"))
      (node (ref "U2") (pin "P10") (pinfunction "GND_P10") (pintype "bidirectional"))
      (node (ref "U2") (pin "P19") (pinfunction "GND_P19") (pintype "bidirectional"))
      (node (ref "U3") (pin "G1") (pinfunction "DVSS_G1") (pintype "bidirectional"))
      (node (ref "U3") (pin "G2") (pinfunction "DVSS_G2") (pintype "bidirectional"))
      (node (ref "U3") (pin "G3") (pinfunction "DVSS_G3") (pintype "bidirectional"))
      (node (ref "U3") (pin "G4") (pinfunction "DVSS_G4") (pintype "bidirectional"))
      (node (ref "U3") (pin "G5") (pinfunction "DVSS_G5") (pintype "bidirectional"))
      (node (ref "U3") (pin "G6") (pinfunction "DVSS_G6") (pintype "bidirectional"))
      (node (ref "U3") (pin "G7") (pinfunction "DVSS_G7") (pintype "bidirectional"))
      (node (ref "U3") (pin "G8") (pinfunction "DVSS_G8") (pintype "bidirectional"))
      (node (ref "U3") (pin "G9") (pinfunction "DVSS_G9") (pintype "bidirectional"))
      (node (ref "U3") (pin "P19") (pinfunction "DVSS_P19") (pintype "bidirectional"))
      (node (ref "U3") (pin "P23") (pinfunction "AVSS_P23") (pintype "bidirectional"))
      (node (ref "U3") (pin "PAD") (pinfunction "DVSS_PAD") (pintype "bidirectional"))
      (node (ref "U4") (pin "PAD") (pinfunction "GND_PAD") (pintype "bidirectional"))
      (node (ref "X1") (pin "P2") (pinfunction "G1_P2") (pintype "bidirectional"))
      (node (ref "X1") (pin "P4") (pinfunction "G2_P4") (pintype "bidirectional"))
    )
    (net (code "7") (name "IPC_MISO") (class "Default")
      (node (ref "SV1") (pin "5") (pinfunction "5_5") (pintype "passive"))
      (node (ref "U4") (pin "P40") (pinfunction "IPCMISO_P40") (pintype "bidirectional"))
    )
    (net (code "8") (name "IPC_MOSI") (class "Default")
      (node (ref "SV1") (pin "4") (pinfunction "4_4") (pintype "passive"))
      (node (ref "U4") (pin "P42") (pinfunction "IPCMOSI_P42") (pintype "bidirectional"))
    )
    (net (code "9") (name "IPC_SCK") (class "Default")
      (node (ref "SV1") (pin "3") (pinfunction "3_3") (pintype "passive"))
      (node (ref "U4") (pin "P44") (pinfunction "IPCSCK_P44") (pintype "bidirectional"))
    )
    (net (code "10") (name "IPC_SS") (class "Default")
      (node (ref "SV1") (pin "1") (pinfunction "1_1") (pintype "passive"))
      (node (ref "U4") (pin "P45") (pinfunction "IPCSS_P45") (pintype "bidirectional"))
    )
    (net (code "11") (name "I_SENSE") (class "Default")
      (node (ref "R37") (pin "2") (pinfunction "2_2") (pintype "passive"))
      (node (ref "TP4") (pin "P$1") (pinfunction "P$1_P$1") (pintype "bidirectional"))
      (node (ref "U3") (pin "P6") (pinfunction "P1.5/TB0.2/UCACLK_P6") (pintype "bidirectional"))
      (node (ref "U4") (pin "P18") (pinfunction "A2_P18") (pintype "bidirectional"))
      (node (ref "U7") (pin "P7") (pinfunction "OUT_P7") (pintype "bidirectional"))
    )
    (net (code "12") (name "LTC_RCTS") (class "Default")
      (node (ref "U4") (pin "P67") (pinfunction "URCTS_P67") (pintype "bidirectional"))
    )
    (net (code "13") (name "LTC_RRTS") (class "Default")
      (node (ref "R46") (pin "2") (pinfunction "2_2") (pintype "passive"))
      (node (ref "U4") (pin "P66") (pinfunction "URRTS_P66") (pintype "bidirectional"))
    )
    (net (code "14") (name "LTC_RX") (class "Default")
      (node (ref "R33") (pin "1") (pinfunction "1_1") (pintype "passive"))
      (node (ref "R47") (pin "2") (pinfunction "2_2") (pintype "passive"))
      (node (ref "TP13") (pin "P$1") (pinfunction "P$1_P$1") (pintype "bidirectional"))
      (node (ref "U3") (pin "P13") (pinfunction "P2.0/UCATX/MOSI_P13") (pintype "bidirectional"))
      (node (ref "U4") (pin "P68") (pinfunction "URX_P68") (pintype "bidirectional"))
    )
    (net (code "15") (name "LTC_SLEEP") (class "Default")
      (node (ref "R44") (pin "2") (pinfunction "2_2") (pintype "passive"))
      (node (ref "U3") (pin "P15") (pinfunction "P2.2/UCBCLK_P15") (pintype "bidirectional"))
      (node (ref "U4") (pin "P35") (pinfunction "SLEEP_P35") (pintype "bidirectional"))
    )
    (net (code "16") (name "LTC_TCTS") (class "Default")
      (node (ref "R48") (pin "2") (pinfunction "2_2") (pintype "passive"))
      (node (ref "U4") (pin "P70") (pinfunction "UTCTS_P70") (pintype "bidirectional"))
    )
    (net (code "17") (name "LTC_TIME") (class "Default")
      (node (ref "R45") (pin "1") (pinfunction "1_1") (pintype "passive"))
      (node (ref "U4") (pin "P72") (pinfunction "TIME_P72") (pintype "bidirectional"))
    )
    (net (code "18") (name "LTC_TRTS") (class "Default")
      (node (ref "U4") (pin "P69") (pinfunction "UTRTS_P69") (pintype "bidirectional"))
    )
    (net (code "19") (name "LTC_TX") (class "Default")
      (node (ref "R34") (pin "1") (pinfunction "1_1") (pintype "passive"))
      (node (ref "TP12") (pin "P$1") (pinfunction "P$1_P$1") (pintype "bidirectional"))
      (node (ref "U3") (pin "P14") (pinfunction "P2.1/TB0.0/UCARX/MISO_P14") (pintype "bidirectional"))
      (node (ref "U4") (pin "P71") (pinfunction "UTX_P71") (pintype "bidirectional"))
    )
    (net (code "20") (name "METER_EN") (class "Default")
      (node (ref "Q1") (pin "P1") (pinfunction "G_P1") (pintype "passive"))
      (node (ref "R49") (pin "2") (pinfunction "2_2") (pintype "passive"))
      (node (ref "U3") (pin "P17") (pinfunction "P1.7/TA1.0/UCBSCL/MISO_P17") (pintype "bidirectional"))
    )
    (net (code "21") (name "NRST") (class "Default")
      (node (ref "SV1") (pin "6") (pinfunction "6_6") (pintype "passive"))
      (node (ref "U4") (pin "P22") (pinfunction "RST_P22") (pintype "bidirectional"))
    )
    (net (code "22") (name "Net-(C1-Pad1)") (class "Default")
      (node (ref "C1") (pin "1") (pinfunction "1_1") (pintype "passive"))
      (node (ref "C2") (pin "1") (pinfunction "1_1") (pintype "passive"))
      (node (ref "R2") (pin "1") (pinfunction "1_1") (pintype "passive"))
      (node (ref "R4") (pin "1") (pinfunction "1_1") (pintype "passive"))
      (node (ref "R8") (pin "2") (pinfunction "2_2") (pintype "passive"))
    )
    (net (code "23") (name "Net-(C30-Pad1)") (class "Default")
      (node (ref "C30") (pin "1") (pinfunction "1_1") (pintype "passive"))
      (node (ref "C31") (pin "1") (pinfunction "1_1") (pintype "passive"))
      (node (ref "L4") (pin "1") (pinfunction "1_1") (pintype "passive"))
    )
    (net (code "24") (name "Net-(C31-Pad2)") (class "Default")
      (node (ref "C31") (pin "2") (pinfunction "2_2") (pintype "passive"))
      (node (ref "Y1") (pin "P1") (pinfunction "P1_P1") (pintype "bidirectional"))
    )
    (net (code "25") (name "Net-(D1-PadA)") (class "Default")
      (node (ref "D1") (pin "A") (pinfunction "A_A") (pintype "passive"))
      (node (ref "D2") (pin "C") (pinfunction "C_C") (pintype "passive"))
      (node (ref "R2") (pin "2") (pinfunction "2_2") (pintype "passive"))
    )
    (net (code "26") (name "Net-(D3-PadP1)") (class "Default")
      (node (ref "D3") (pin "P1") (pinfunction "P1_P1") (pintype "passive"))
      (node (ref "R5") (pin "1") (pinfunction "1_1") (pintype "passive"))
    )
    (net (code "27") (name "Net-(D3-PadP2)") (class "Default")
      (node (ref "D3") (pin "P2") (pinfunction "P2_P2") (pintype "passive"))
      (node (ref "R6") (pin "2") (pinfunction "2_2") (pintype "passive"))
    )
    (net (code "28") (name "Net-(D3-PadP4)") (class "Default")
      (node (ref "D3") (pin "P4") (pinfunction "P4_P4") (pintype "passive"))
      (node (ref "R4") (pin "2") (pinfunction "2_2") (pintype "passive"))
    )
    (net (code "29") (name "Net-(J21-P)") (class "Default")
      (node (ref "J21") (pin "L") (pinfunction "P_L") (pintype "bidirectional"))
      (node (ref "R3") (pin "1") (pinfunction "1_1") (pintype "passive"))
      (node (ref "R6") (pin "1") (pinfunction "1_1") (pintype "passive"))
    )
    (net (code "30") (name "Net-(J21-PadN)") (class "Default")
      (node (ref "J21") (pin "N") (pinfunction "N_N") (pintype "bidirectional"))
      (node (ref "R1") (pin "1") (pinfunction "1_1") (pintype "passive"))
    )
    (net (code "31") (name "Net-(L3-Pad2)") (class "Default")
      (node (ref "L3") (pin "2") (pinfunction "2_2") (pintype "passive"))
      (node (ref "R14") (pin "1") (pinfunction "1_1") (pintype "passive"))
      (node (ref "R15") (pin "2") (pinfunction "2_2") (pintype "passive"))
      (node (ref "R16") (pin "2") (pinfunction "2_2") (pintype "passive"))
    )
    (net (code "32") (name "Net-(L5-Pad1)") (class "Default")
      (node (ref "L5") (pin "1") (pinfunction "1_1") (pintype "passive"))
      (node (ref "L6") (pin "1") (pinfunction "1_1") (pintype "passive"))
      (node (ref "Y2") (pin "P1") (pinfunction "P1_P1") (pintype "bidirectional"))
    )
    (net (code "33") (name "Net-(LED1-PadA)") (class "Default")
      (node (ref "LED1") (pin "A") (pinfunction "A_A") (pintype "passive"))
      (node (ref "R10") (pin "1") (pinfunction "1_1") (pintype "passive"))
    )
    (net (code "34") (name "Net-(LED2-PadA)") (class "Default")
      (node (ref "LED2") (pin "A") (pinfunction "A_A") (pintype "passive"))
      (node (ref "R23") (pin "1") (pinfunction "1_1") (pintype "passive"))
    )
    (net (code "35") (name "Net-(Q2-D)") (class "Default")
      (node (ref "LED1") (pin "C") (pinfunction "C_C") (pintype "passive"))
      (node (ref "Q2") (pin "P3") (pinfunction "D_P3") (pintype "passive"))
    )
    (net (code "36") (name "Net-(Q3-D)") (class "Default")
      (node (ref "LED2") (pin "C") (pinfunction "C_C") (pintype "passive"))
      (node (ref "Q3") (pin "P3") (pinfunction "D_P3") (pintype "passive"))
    )
    (net (code "37") (name "Net-(R18-Pad2)") (class "Default")
      (node (ref "R18") (pin "2") (pinfunction "2_2") (pintype "passive"))
      (node (ref "R36") (pin "PW") (pinfunction "PW_PW") (pintype "passive"))
    )
    (net (code "38") (name "Net-(R35-Pad2)") (class "Default")
      (node (ref "R35") (pin "2") (pinfunction "2_2") (pintype "passive"))
      (node (ref "R42") (pin "P2") (pinfunction "P2_P2") (pintype "passive"))
    )
    (net (code "39") (name "Net-(R38-Pad2)") (class "Default")
      (node (ref "R38") (pin "2") (pinfunction "2_2") (pintype "passive"))
      (node (ref "R41") (pin "PW") (pinfunction "PW_PW") (pintype "passive"))
    )
    (net (code "40") (name "Net-(U1-FB)") (class "Default")
      (node (ref "C4") (pin "2") (pinfunction "2_2") (pintype "passive"))
      (node (ref "R7") (pin "1") (pinfunction "1_1") (pintype "passive"))
      (node (ref "R9") (pin "2") (pinfunction "2_2") (pintype "passive"))
      (node (ref "U1") (pin "P3") (pinfunction "FB_P3") (pintype "bidirectional"))
    )
    (net (code "41") (name "Net-(U1-SW)") (class "Default")
      (node (ref "L1") (pin "2") (pinfunction "2_2") (pintype "passive"))
      (node (ref "U1") (pin "P1") (pinfunction "SW_P1") (pintype "bidirectional"))
    )
    (net (code "42") (name "Net-(U1-VOUT)") (class "Default")
      (node (ref "C10") (pin "1") (pinfunction "1_1") (pintype "passive"))
      (node (ref "C4") (pin "1") (pinfunction "1_1") (pintype "passive"))
      (node (ref "C9") (pin "1") (pinfunction "1_1") (pintype "passive"))
      (node (ref "CS+") (pin "P$1") (pinfunction "P$1_P$1") (pintype "bidirectional"))
      (node (ref "L1") (pin "1") (pinfunction "1_1") (pintype "passive"))
      (node (ref "R13") (pin "1") (pinfunction "1_1") (pintype "passive"))
      (node (ref "R7") (pin "2") (pinfunction "2_2") (pintype "passive"))
      (node (ref "U1") (pin "P2") (pinfunction "VOUT_P2") (pintype "bidirectional"))
    )
    (net (code "43") (name "Net-(U2-BBOUT)") (class "Default")
      (node (ref "C33") (pin "2") (pinfunction "2_2") (pintype "passive"))
      (node (ref "U2") (pin "P5") (pinfunction "BBOUT_P5") (pintype "bidirectional"))
    )
    (net (code "44") (name "Net-(U2-CMPIN)") (class "Default")
      (node (ref "C33") (pin "1") (pinfunction "1_1") (pintype "passive"))
      (node (ref "U2") (pin "P6") (pinfunction "CMPIN_P6") (pintype "bidirectional"))
    )
    (net (code "45") (name "Net-(U2-LPFADJ)") (class "Default")
      (node (ref "R29") (pin "2") (pinfunction "2_2") (pintype "passive"))
      (node (ref "U2") (pin "P9") (pinfunction "LPFADJ_P9") (pintype "bidirectional"))
    )
    (net (code "46") (name "Net-(U2-PRATE)") (class "Default")
      (node (ref "R28") (pin "2") (pinfunction "2_2") (pintype "passive"))
      (node (ref "U2") (pin "P14") (pinfunction "PRATE_P14") (pintype "bidirectional"))
    )
    (net (code "47") (name "Net-(U2-PWIDTH)") (class "Default")
      (node (ref "R22") (pin "2") (pinfunction "2_2") (pintype "passive"))
      (node (ref "U2") (pin "P15") (pinfunction "PWIDTH_P15") (pintype "bidirectional"))
    )
    (net (code "48") (name "Net-(U2-REF)") (class "Default")
      (node (ref "R26") (pin "1") (pinfunction "1_1") (pintype "passive"))
      (node (ref "U2") (pin "P11") (pinfunction "REF_P11") (pintype "bidirectional"))
      (node (ref "U2") (pin "P13") (pinfunction "THLD1_P13") (pintype "bidirectional"))
    )
    (net (code "49") (name "Net-(U2-RFIO)") (class "Default")
      (node (ref "L5") (pin "2") (pinfunction "2_2") (pintype "passive"))
      (node (ref "U2") (pin "P20") (pinfunction "RFIO_P20") (pintype "bidirectional"))
    )
    (net (code "50") (name "Net-(U2-TXMOD)") (class "Default")
      (node (ref "R30") (pin "2") (pinfunction "2_2") (pintype "passive"))
      (node (ref "U2") (pin "P8") (pinfunction "TXMOD_P8") (pintype "bidirectional"))
    )
    (net (code "51") (name "Net-(U2-VCC1)") (class "Default")
      (node (ref "L7") (pin "2") (pinfunction "2_2") (pintype "passive"))
      (node (ref "U2") (pin "P2") (pinfunction "VCC1_P2") (pintype "bidirectional"))
    )
    (net (code "52") (name "Net-(U3-VCORE)") (class "Default")
      (node (ref "C16") (pin "2") (pinfunction "2_2") (pintype "passive"))
      (node (ref "U3") (pin "P18") (pinfunction "VCORE_P18") (pintype "bidirectional"))
    )
    (net (code "53") (name "Net-(U3-XIN)") (class "Default")
      (node (ref "C8") (pin "2") (pinfunction "2_2") (pintype "passive"))
      (node (ref "U3") (pin "P21") (pinfunction "XIN_P21") (pintype "bidirectional"))
      (node (ref "X3") (pin "2") (pinfunction "P2_2") (pintype "bidirectional"))
    )
    (net (code "54") (name "Net-(U3-XOUT)") (class "Default")
      (node (ref "C34") (pin "2") (pinfunction "2_2") (pintype "passive"))
      (node (ref "U3") (pin "P22") (pinfunction "XOUT_P22") (pintype "bidirectional"))
      (node (ref "X3") (pin "1") (pinfunction "P1_1") (pintype "bidirectional"))
    )
    (net (code "55") (name "Net-(U4A-CAP_PA1M)") (class "Default")
      (node (ref "C5") (pin "2") (pinfunction "2_2") (pintype "passive"))
      (node (ref "U4") (pin "P3") (pinfunction "CAP_PA1M_P3") (pintype "bidirectional"))
    )
    (net (code "56") (name "Net-(U4A-CAP_PA1P)") (class "Default")
      (node (ref "C5") (pin "1") (pinfunction "1_1") (pintype "passive"))
      (node (ref "U4") (pin "P2") (pinfunction "CAP_PA1P_P2") (pintype "bidirectional"))
    )
    (net (code "57") (name "Net-(U4A-CAP_PA2M)") (class "Default")
      (node (ref "C6") (pin "2") (pinfunction "2_2") (pintype "passive"))
      (node (ref "U4") (pin "P4") (pinfunction "CAP_PA2M_P4") (pintype "bidirectional"))
    )
    (net (code "58") (name "Net-(U4A-CAP_PA2P)") (class "Default")
      (node (ref "C6") (pin "1") (pinfunction "1_1") (pintype "passive"))
      (node (ref "U4") (pin "P5") (pinfunction "CAP_PA2P_P5") (pintype "bidirectional"))
    )
    (net (code "59") (name "Net-(U4A-CAP_PA3M)") (class "Default")
      (node (ref "C11") (pin "2") (pinfunction "2_2") (pintype "passive"))
      (node (ref "U4") (pin "P7") (pinfunction "CAP_PA3M_P7") (pintype "bidirectional"))
    )
    (net (code "60") (name "Net-(U4A-CAP_PA3P)") (class "Default")
      (node (ref "C11") (pin "1") (pinfunction "1_1") (pintype "passive"))
      (node (ref "U4") (pin "P6") (pinfunction "CAP_PA3P_P6") (pintype "bidirectional"))
    )
    (net (code "61") (name "Net-(U4A-CAP_PA4M)") (class "Default")
      (node (ref "C12") (pin "2") (pinfunction "2_2") (pintype "passive"))
      (node (ref "U4") (pin "P8") (pinfunction "CAP_PA4M_P8") (pintype "bidirectional"))
    )
    (net (code "62") (name "Net-(U4A-CAP_PA4P)") (class "Default")
      (node (ref "C12") (pin "1") (pinfunction "1_1") (pintype "passive"))
      (node (ref "U4") (pin "P9") (pinfunction "CAP_PA4P_P9") (pintype "bidirectional"))
    )
    (net (code "63") (name "Net-(U4A-CAP_PR1M)") (class "Default")
      (node (ref "C13") (pin "2") (pinfunction "2_2") (pintype "passive"))
      (node (ref "U4") (pin "P63") (pinfunction "CAP_PR1M_P63") (pintype "bidirectional"))
    )
    (net (code "64") (name "Net-(U4A-CAP_PR1P)") (class "Default")
      (node (ref "C13") (pin "1") (pinfunction "1_1") (pintype "passive"))
      (node (ref "U4") (pin "P64") (pinfunction "CAP_PR1P_P64") (pintype "bidirectional"))
    )
    (net (code "65") (name "Net-(U4A-CAP_PR2M)") (class "Default")
      (node (ref "C17") (pin "2") (pinfunction "2_2") (pintype "passive"))
      (node (ref "U4") (pin "P62") (pinfunction "CAP_PR2M_P62") (pintype "bidirectional"))
    )
    (net (code "66") (name "Net-(U4A-CAP_PR2P)") (class "Default")
      (node (ref "C17") (pin "1") (pinfunction "1_1") (pintype "passive"))
      (node (ref "U4") (pin "P61") (pinfunction "CAP_PR2P_P61") (pintype "bidirectional"))
    )
    (net (code "67") (name "Net-(U4A-CAP_PR3M)") (class "Default")
      (node (ref "C18") (pin "2") (pinfunction "2_2") (pintype "passive"))
      (node (ref "U4") (pin "P59") (pinfunction "CAP_PR3M_P59") (pintype "bidirectional"))
    )
    (net (code "68") (name "Net-(U4A-CAP_PR3P)") (class "Default")
      (node (ref "C18") (pin "1") (pinfunction "1_1") (pintype "passive"))
      (node (ref "U4") (pin "P60") (pinfunction "CAP_PR3P_P60") (pintype "bidirectional"))
    )
    (net (code "69") (name "Net-(U4A-CAP_PR4M)") (class "Default")
      (node (ref "C19") (pin "2") (pinfunction "2_2") (pintype "passive"))
      (node (ref "U4") (pin "P58") (pinfunction "CAP_PR4M_P58") (pintype "bidirectional"))
    )
    (net (code "70") (name "Net-(U4A-CAP_PR4P)") (class "Default")
      (node (ref "C19") (pin "1") (pinfunction "1_1") (pintype "passive"))
      (node (ref "U4") (pin "P57") (pinfunction "CAP_PR4P_P57") (pintype "bidirectional"))
    )
    (net (code "71") (name "Net-(U4B-ANT)") (class "Default")
      (node (ref "C29") (pin "1") (pinfunction "1_1") (pintype "passive"))
      (node (ref "L4") (pin "2") (pinfunction "2_2") (pintype "passive"))
      (node (ref "U4") (pin "P14") (pinfunction "ANT_P14") (pintype "bidirectional"))
    )
    (net (code "72") (name "Net-(U4B-OSCAIN)") (class "Default")
      (node (ref "U4") (pin "P28") (pinfunction "OSCAIN_P28") (pintype "bidirectional"))
      (node (ref "X1") (pin "P3") (pinfunction "P2_P3") (pintype "bidirectional"))
    )
    (net (code "73") (name "Net-(U4B-OSCAOUT)") (class "Default")
      (node (ref "U4") (pin "P29") (pinfunction "OSCAOUT_P29") (pintype "bidirectional"))
      (node (ref "X1") (pin "P1") (pinfunction "P1_P1") (pintype "bidirectional"))
    )
    (net (code "74") (name "Net-(U4B-OSCBIN)") (class "Default")
      (node (ref "U4") (pin "P20") (pinfunction "OSCBIN_P20") (pintype "bidirectional"))
      (node (ref "X2") (pin "P2") (pinfunction "P2_P2") (pintype "bidirectional"))
    )
    (net (code "75") (name "Net-(U4B-OSCBOUT)") (class "Default")
      (node (ref "U4") (pin "P19") (pinfunction "OSCBOUT_P19") (pintype "bidirectional"))
      (node (ref "X2") (pin "P1") (pinfunction "P1_P1") (pintype "bidirectional"))
    )
    (net (code "76") (name "Net-(U4B-R_INHIBIT)") (class "Default")
      (node (ref "R43") (pin "1") (pinfunction "1_1") (pintype "passive"))
      (node (ref "U4") (pin "P1") (pinfunction "R_INHIBIT_P1") (pintype "bidirectional"))
    )
    (net (code "77") (name "Net-(U4B-TCK)") (class "Default")
      (node (ref "TP2") (pin "P$1") (pinfunction "P$1_P$1") (pintype "bidirectional"))
      (node (ref "U4") (pin "P26") (pinfunction "TCK_P26") (pintype "bidirectional"))
    )
    (net (code "78") (name "Net-(U4B-TDI)") (class "Default")
      (node (ref "TP7") (pin "P$1") (pinfunction "P$1_P$1") (pintype "bidirectional"))
      (node (ref "U4") (pin "P23") (pinfunction "TDI_P23") (pintype "bidirectional"))
    )
    (net (code "79") (name "Net-(U4B-TDO)") (class "Default")
      (node (ref "TP6") (pin "P$1") (pinfunction "P$1_P$1") (pintype "bidirectional"))
      (node (ref "U4") (pin "P24") (pinfunction "TDO_P24") (pintype "bidirectional"))
    )
    (net (code "80") (name "Net-(U4B-TMS)") (class "Default")
      (node (ref "TP5") (pin "P$1") (pinfunction "P$1_P$1") (pintype "bidirectional"))
      (node (ref "U4") (pin "P25") (pinfunction "TMS_P25") (pintype "bidirectional"))
    )
    (net (code "81") (name "Net-(U4B-VCORE)") (class "Default")
      (node (ref "C21") (pin "1") (pinfunction "1_1") (pintype "passive"))
      (node (ref "U4") (pin "P31") (pinfunction "VCORE_P31") (pintype "bidirectional"))
    )
    (net (code "82") (name "Net-(U4B-VDDA)") (class "Default")
      (node (ref "C22") (pin "1") (pinfunction "1_1") (pintype "passive"))
      (node (ref "U4") (pin "P30") (pinfunction "VDDA_P30") (pintype "bidirectional"))
    )
    (net (code "83") (name "Net-(U4B-VDDPA)") (class "Default")
      (node (ref "C23") (pin "1") (pinfunction "1_1") (pintype "passive"))
      (node (ref "U4") (pin "P10") (pinfunction "VDDPA_P10") (pintype "bidirectional"))
    )
    (net (code "84") (name "Net-(U4B-VOSC)") (class "Default")
      (node (ref "C20") (pin "1") (pinfunction "1_1") (pintype "passive"))
      (node (ref "U4") (pin "P32") (pinfunction "VOSC_P32") (pintype "bidirectional"))
    )
    (net (code "85") (name "Net-(U4B-VPP)") (class "Default")
      (node (ref "TP8") (pin "P$1") (pinfunction "P$1_P$1") (pintype "bidirectional"))
      (node (ref "U4") (pin "P54") (pinfunction "VPP_P54") (pintype "bidirectional"))
    )
    (net (code "86") (name "Net-(U4B-VPRIME)") (class "Default")
      (node (ref "C24") (pin "1") (pinfunction "1_1") (pintype "passive"))
      (node (ref "U4") (pin "P56") (pinfunction "VPRIME_P56") (pintype "bidirectional"))
    )
    (net (code "87") (name "Net-(U4B-VSUPPLY)") (class "Default")
      (node (ref "C25") (pin "1") (pinfunction "1_1") (pintype "passive"))
      (node (ref "C26") (pin "1") (pinfunction "1_1") (pintype "passive"))
      (node (ref "L2") (pin "2") (pinfunction "2_2") (pintype "passive"))
      (node (ref "U4") (pin "P65") (pinfunction "VSUPPLY_P65") (pintype "bidirectional"))
    )
    (net (code "88") (name "Net-(U5-IN+)") (class "Default")
      (node (ref "L3") (pin "1") (pinfunction "1_1") (pintype "passive"))
      (node (ref "R14") (pin "2") (pinfunction "2_2") (pintype "passive"))
      (node (ref "U5") (pin "P1") (pinfunction "IN+_P1") (pintype "bidirectional"))
    )
    (net (code "89") (name "Net-(U5-IN-)") (class "Default")
      (node (ref "R17") (pin "1") (pinfunction "1_1") (pintype "passive"))
      (node (ref "R36") (pin "P2") (pinfunction "P2_P2") (pintype "passive"))
      (node (ref "U5") (pin "P3") (pinfunction "IN-_P3") (pintype "bidirectional"))
    )
    (net (code "90") (name "Net-(U5-OUT)") (class "Default")
      (node (ref "C39") (pin "1") (pinfunction "1_1") (pintype "passive"))
      (node (ref "R17") (pin "2") (pinfunction "2_2") (pintype "passive"))
      (node (ref "TP1") (pin "P$1") (pinfunction "P$1_P$1") (pintype "bidirectional"))
      (node (ref "U5") (pin "P4") (pinfunction "OUT_P4") (pintype "bidirectional"))
    )
    (net (code "91") (name "Net-(U6-IN+)") (class "Default")
      (node (ref "R20") (pin "1") (pinfunction "1_1") (pintype "passive"))
      (node (ref "R21") (pin "2") (pinfunction "2_2") (pintype "passive"))
      (node (ref "U6") (pin "P1") (pinfunction "IN+_P1") (pintype "bidirectional"))
    )
    (net (code "92") (name "Net-(U6-IN-)") (class "Default")
      (node (ref "RF") (pin "1") (pinfunction "1_1") (pintype "passive"))
      (node (ref "RI1") (pin "2") (pinfunction "2_2") (pintype "passive"))
      (node (ref "RI2") (pin "2") (pinfunction "2_2") (pintype "passive"))
      (node (ref "U6") (pin "P3") (pinfunction "IN-_P3") (pintype "bidirectional"))
    )
    (net (code "93") (name "Net-(U7A-IN+)") (class "Default")
      (node (ref "R39") (pin "P2") (pinfunction "P2_P2") (pintype "passive"))
      (node (ref "R40") (pin "1") (pinfunction "1_1") (pintype "passive"))
      (node (ref "U7") (pin "P3") (pinfunction "IN+_P3") (pintype "bidirectional"))
    )
    (net (code "94") (name "Net-(U7A-IN-)") (class "Default")
      (node (ref "R35") (pin "1") (pinfunction "1_1") (pintype "passive"))
      (node (ref "U7") (pin "P1") (pinfunction "OUT_P1") (pintype "bidirectional"))
      (node (ref "U7") (pin "P2") (pinfunction "IN-_P2") (pintype "bidirectional"))
    )
    (net (code "95") (name "Net-(U7B-IN+)") (class "Default")
      (node (ref "C39") (pin "2") (pinfunction "2_2") (pintype "passive"))
      (node (ref "R42") (pin "PW") (pinfunction "PW_PW") (pintype "passive"))
      (node (ref "TP9") (pin "P$1") (pinfunction "P$1_P$1") (pintype "bidirectional"))
      (node (ref "U7") (pin "P5") (pinfunction "IN+_P5") (pintype "bidirectional"))
    )
    (net (code "96") (name "Net-(U7B-IN-)") (class "Default")
      (node (ref "R37") (pin "1") (pinfunction "1_1") (pintype "passive"))
      (node (ref "R41") (pin "P2") (pinfunction "P2_P2") (pintype "passive"))
      (node (ref "U7") (pin "P6") (pinfunction "IN-_P6") (pintype "bidirectional"))
    )
    (net (code "97") (name "RST") (class "Default")
      (node (ref "J1") (pin "P10") (pinfunction "11_P10") (pintype "bidirectional"))
      (node (ref "R19") (pin "1") (pinfunction "1_1") (pintype "passive"))
      (node (ref "U3") (pin "P12") (pinfunction "RST_P12") (pintype "bidirectional"))
    )
    (net (code "98") (name "RXDATA") (class "Default")
      (node (ref "R34") (pin "2") (pinfunction "2_2") (pintype "passive"))
      (node (ref "TP11") (pin "P$1") (pinfunction "P$1_P$1") (pintype "bidirectional"))
      (node (ref "U2") (pin "P7") (pinfunction "RXDATA_P7") (pintype "bidirectional"))
      (node (ref "U3") (pin "P16") (pinfunction "P1.6/TA0.0/UCBSDA/MOSI_P16") (pintype "bidirectional"))
    )
    (net (code "99") (name "TCK") (class "Default")
      (node (ref "J1") (pin "P7") (pinfunction "7_P7") (pintype "bidirectional"))
      (node (ref "Q2") (pin "P1") (pinfunction "G_P1") (pintype "passive"))
      (node (ref "U3") (pin "P10") (pinfunction "TCK_P10") (pintype "bidirectional"))
    )
    (net (code "100") (name "TDI") (class "Default")
      (node (ref "J1") (pin "P3") (pinfunction "3_P3") (pintype "bidirectional"))
      (node (ref "Q3") (pin "P1") (pinfunction "G_P1") (pintype "passive"))
      (node (ref "U3") (pin "P8") (pinfunction "TDI_P8") (pintype "bidirectional"))
    )
    (net (code "101") (name "TDO") (class "Default")
      (node (ref "J1") (pin "P1") (pinfunction "1_P1") (pintype "bidirectional"))
      (node (ref "U3") (pin "P7") (pinfunction "TDO_P7") (pintype "bidirectional"))
    )
    (net (code "102") (name "TEST") (class "Default")
      (node (ref "J1") (pin "P8") (pinfunction "8_P8") (pintype "bidirectional"))
      (node (ref "U3") (pin "P11") (pinfunction "TEST_P11") (pintype "bidirectional"))
    )
    (net (code "103") (name "TMS") (class "Default")
      (node (ref "J1") (pin "P5") (pinfunction "5_P5") (pintype "bidirectional"))
      (node (ref "U3") (pin "P9") (pinfunction "TMS_P9") (pintype "bidirectional"))
    )
    (net (code "104") (name "TXMOD") (class "Default")
      (node (ref "R30") (pin "1") (pinfunction "1_1") (pintype "passive"))
      (node (ref "R33") (pin "2") (pinfunction "2_2") (pintype "passive"))
      (node (ref "TP10") (pin "P$1") (pinfunction "P$1_P$1") (pintype "bidirectional"))
      (node (ref "U3") (pin "P3") (pinfunction "P1.2/TA1.1/A2_P3") (pintype "bidirectional"))
    )
    (net (code "105") (name "UC_RX") (class "Default")
      (node (ref "SV1") (pin "10") (pinfunction "10_10") (pintype "passive"))
      (node (ref "U4") (pin "P38") (pinfunction "UCRX_P38") (pintype "bidirectional"))
    )
    (net (code "106") (name "UC_TX") (class "Default")
      (node (ref "SV1") (pin "9") (pinfunction "9_9") (pintype "passive"))
      (node (ref "U4") (pin "P37") (pinfunction "UCTX_P37") (pintype "bidirectional"))
    )
    (net (code "107") (name "VCC") (class "Default")
      (node (ref "C3") (pin "1") (pinfunction "1_1") (pintype "passive"))
      (node (ref "C32") (pin "1") (pinfunction "1_1") (pintype "passive"))
      (node (ref "C7") (pin "1") (pinfunction "1_1") (pintype "passive"))
      (node (ref "D1") (pin "C") (pinfunction "C_C") (pintype "passive"))
      (node (ref "R11") (pin "2") (pinfunction "2_2") (pintype "passive"))
      (node (ref "R3") (pin "2") (pinfunction "2_2") (pintype "passive"))
      (node (ref "R5") (pin "2") (pinfunction "2_2") (pintype "passive"))
      (node (ref "RS+") (pin "P$1") (pinfunction "P$1_P$1") (pintype "bidirectional"))
      (node (ref "U1") (pin "P4") (pinfunction "EN_P4") (pintype "bidirectional"))
      (node (ref "U1") (pin "P5") (pinfunction "VIN_P5") (pintype "bidirectional"))
    )
    (net (code "108") (name "VCC_SENSE") (class "Default")
      (node (ref "R11") (pin "1") (pinfunction "1_1") (pintype "passive"))
      (node (ref "R12") (pin "2") (pinfunction "2_2") (pintype "passive"))
      (node (ref "U3") (pin "P4") (pinfunction "P1.3/TA1.2/A3_P4") (pintype "bidirectional"))
    )
    (net (code "109") (name "VTEST") (class "Default")
      (node (ref "C1") (pin "2") (pinfunction "2_2") (pintype "passive"))
      (node (ref "C2") (pin "2") (pinfunction "2_2") (pintype "passive"))
      (node (ref "HVS") (pin "P$1") (pinfunction "P$1_P$1") (pintype "bidirectional"))
      (node (ref "R1") (pin "2") (pinfunction "2_2") (pintype "passive"))
      (node (ref "R8") (pin "1") (pinfunction "1_1") (pintype "passive"))
      (node (ref "RI1") (pin "1") (pinfunction "1_1") (pintype "passive"))
    )
    (net (code "110") (name "V_SENSE") (class "Default")
      (node (ref "RF") (pin "2") (pinfunction "2_2") (pintype "passive"))
      (node (ref "TP3") (pin "P$1") (pinfunction "P$1_P$1") (pintype "bidirectional"))
      (node (ref "U3") (pin "P5") (pinfunction "P1.4/TB0.1/A4_P5") (pintype "bidirectional"))
      (node (ref "U4") (pin "P17") (pinfunction "A3_P17") (pintype "bidirectional"))
      (node (ref "U6") (pin "P4") (pinfunction "OUT_P4") (pintype "bidirectional"))
    )
    (net (code "111") (name "unconnected-(J1-4-PadP4)") (class "Default")
      (node (ref "J1") (pin "P4") (pinfunction "4_P4") (pintype "bidirectional"))
    )
    (net (code "112") (name "unconnected-(J1-6-PadP6)") (class "Default")
      (node (ref "J1") (pin "P6") (pinfunction "6_P6") (pintype "bidirectional"))
    )
    (net (code "113") (name "unconnected-(R36-PadP1)") (class "Default")
      (node (ref "R36") (pin "P1") (pinfunction "P1_P1") (pintype "passive"))
    )
    (net (code "114") (name "unconnected-(R39-PadP1)") (class "Default")
      (node (ref "R39") (pin "P1") (pinfunction "P1_P1") (pintype "passive"))
    )
    (net (code "115") (name "unconnected-(R41-PadP1)") (class "Default")
      (node (ref "R41") (pin "P1") (pinfunction "P1_P1") (pintype "passive"))
    )
    (net (code "116") (name "unconnected-(R42-PadP1)") (class "Default")
      (node (ref "R42") (pin "P1") (pinfunction "P1_P1") (pintype "passive"))
    )
    (net (code "117") (name "unconnected-(U2-PKDET-PadP4)") (class "Default")
      (node (ref "U2") (pin "P4") (pinfunction "PKDET_P4") (pintype "bidirectional"))
    )
    (net (code "118") (name "unconnected-(U2-THLD2-PadP12)") (class "Default")
      (node (ref "U2") (pin "P12") (pinfunction "THLD2_P12") (pintype "bidirectional"))
    )
    (net (code "119") (name "unconnected-(U4B-LNA_EN-PadP11)") (class "Default")
      (node (ref "U4") (pin "P11") (pinfunction "LNA_EN_P11") (pintype "bidirectional"))
    )
    (net (code "120") (name "unconnected-(U4B-RADIOTX-PadP12)") (class "Default")
      (node (ref "U4") (pin "P12") (pinfunction "RADIOTX_P12") (pintype "bidirectional"))
    )
    (net (code "121") (name "unconnected-(U4B-RADIOTXN-PadP13)") (class "Default")
      (node (ref "U4") (pin "P13") (pinfunction "RADIOTXN_P13") (pintype "bidirectional"))
    )
    (net (code "122") (name "unconnected-(U4B-VBGAP-PadP21)") (class "Default")
      (node (ref "U4") (pin "P21") (pinfunction "VBGAP_P21") (pintype "bidirectional"))
    )
    (net (code "123") (name "unconnected-(U4C-A0-PadP15)") (class "Default")
      (node (ref "U4") (pin "P15") (pinfunction "A0_P15") (pintype "bidirectional"))
    )
    (net (code "124") (name "unconnected-(U4C-A1-PadP16)") (class "Default")
      (node (ref "U4") (pin "P16") (pinfunction "A1_P16") (pintype "bidirectional"))
    )
    (net (code "125") (name "unconnected-(U4C-DP0-PadP36)") (class "Default")
      (node (ref "U4") (pin "P36") (pinfunction "DP0_P36") (pintype "bidirectional"))
    )
    (net (code "126") (name "unconnected-(U4C-DP1-PadP48)") (class "Default")
      (node (ref "U4") (pin "P48") (pinfunction "DP1_P48") (pintype "bidirectional"))
    )
    (net (code "127") (name "unconnected-(U4C-DP2-PadP34)") (class "Default")
      (node (ref "U4") (pin "P34") (pinfunction "DP2_P34") (pintype "bidirectional"))
    )
    (net (code "128") (name "unconnected-(U4C-DP3-PadP33)") (class "Default")
      (node (ref "U4") (pin "P33") (pinfunction "DP3_P33") (pintype "bidirectional"))
    )
    (net (code "129") (name "unconnected-(U4C-DP4-PadP27)") (class "Default")
      (node (ref "U4") (pin "P27") (pinfunction "DP4_P27") (pintype "bidirectional"))
    )
    (net (code "130") (name "unconnected-(U4C-MMISO-PadP39)") (class "Default")
      (node (ref "U4") (pin "P39") (pinfunction "MMISO_P39") (pintype "bidirectional"))
    )
    (net (code "131") (name "unconnected-(U4C-MMOSI-PadP41)") (class "Default")
      (node (ref "U4") (pin "P41") (pinfunction "MMOSI_P41") (pintype "bidirectional"))
    )
    (net (code "132") (name "unconnected-(U4C-MSCK-PadP43)") (class "Default")
      (node (ref "U4") (pin "P43") (pinfunction "MSCK_P43") (pintype "bidirectional"))
    )
    (net (code "133") (name "unconnected-(U4C-MSS0-PadP47)") (class "Default")
      (node (ref "U4") (pin "P47") (pinfunction "MSS0_P47") (pintype "bidirectional"))
    )
    (net (code "134") (name "unconnected-(U4C-MSS1-PadP46)") (class "Default")
      (node (ref "U4") (pin "P46") (pinfunction "MSS1_P46") (pintype "bidirectional"))
    )
    (net (code "135") (name "unconnected-(U4C-PWM0-PadP49)") (class "Default")
      (node (ref "U4") (pin "P49") (pinfunction "PWM0_P49") (pintype "bidirectional"))
    )
    (net (code "136") (name "unconnected-(U4C-SCLK-PadP52)") (class "Default")
      (node (ref "U4") (pin "P52") (pinfunction "SCLK_P52") (pintype "bidirectional"))
    )
    (net (code "137") (name "unconnected-(U4C-SMISO-PadP50)") (class "Default")
      (node (ref "U4") (pin "P50") (pinfunction "SMISO_P50") (pintype "bidirectional"))
    )
    (net (code "138") (name "unconnected-(U4C-SMOSI-PadP51)") (class "Default")
      (node (ref "U4") (pin "P51") (pinfunction "SMOSI_P51") (pintype "bidirectional"))
    )
    (net (code "139") (name "unconnected-(U4C-SSS-PadP53)") (class "Default")
      (node (ref "U4") (pin "P53") (pinfunction "SSS_P53") (pintype "bidirectional"))
    )
  )
)
